# rapidshark-main-breakout-top-mk-1_7-fab.net
KiCad netlist of a schematic drawn in EAGLE
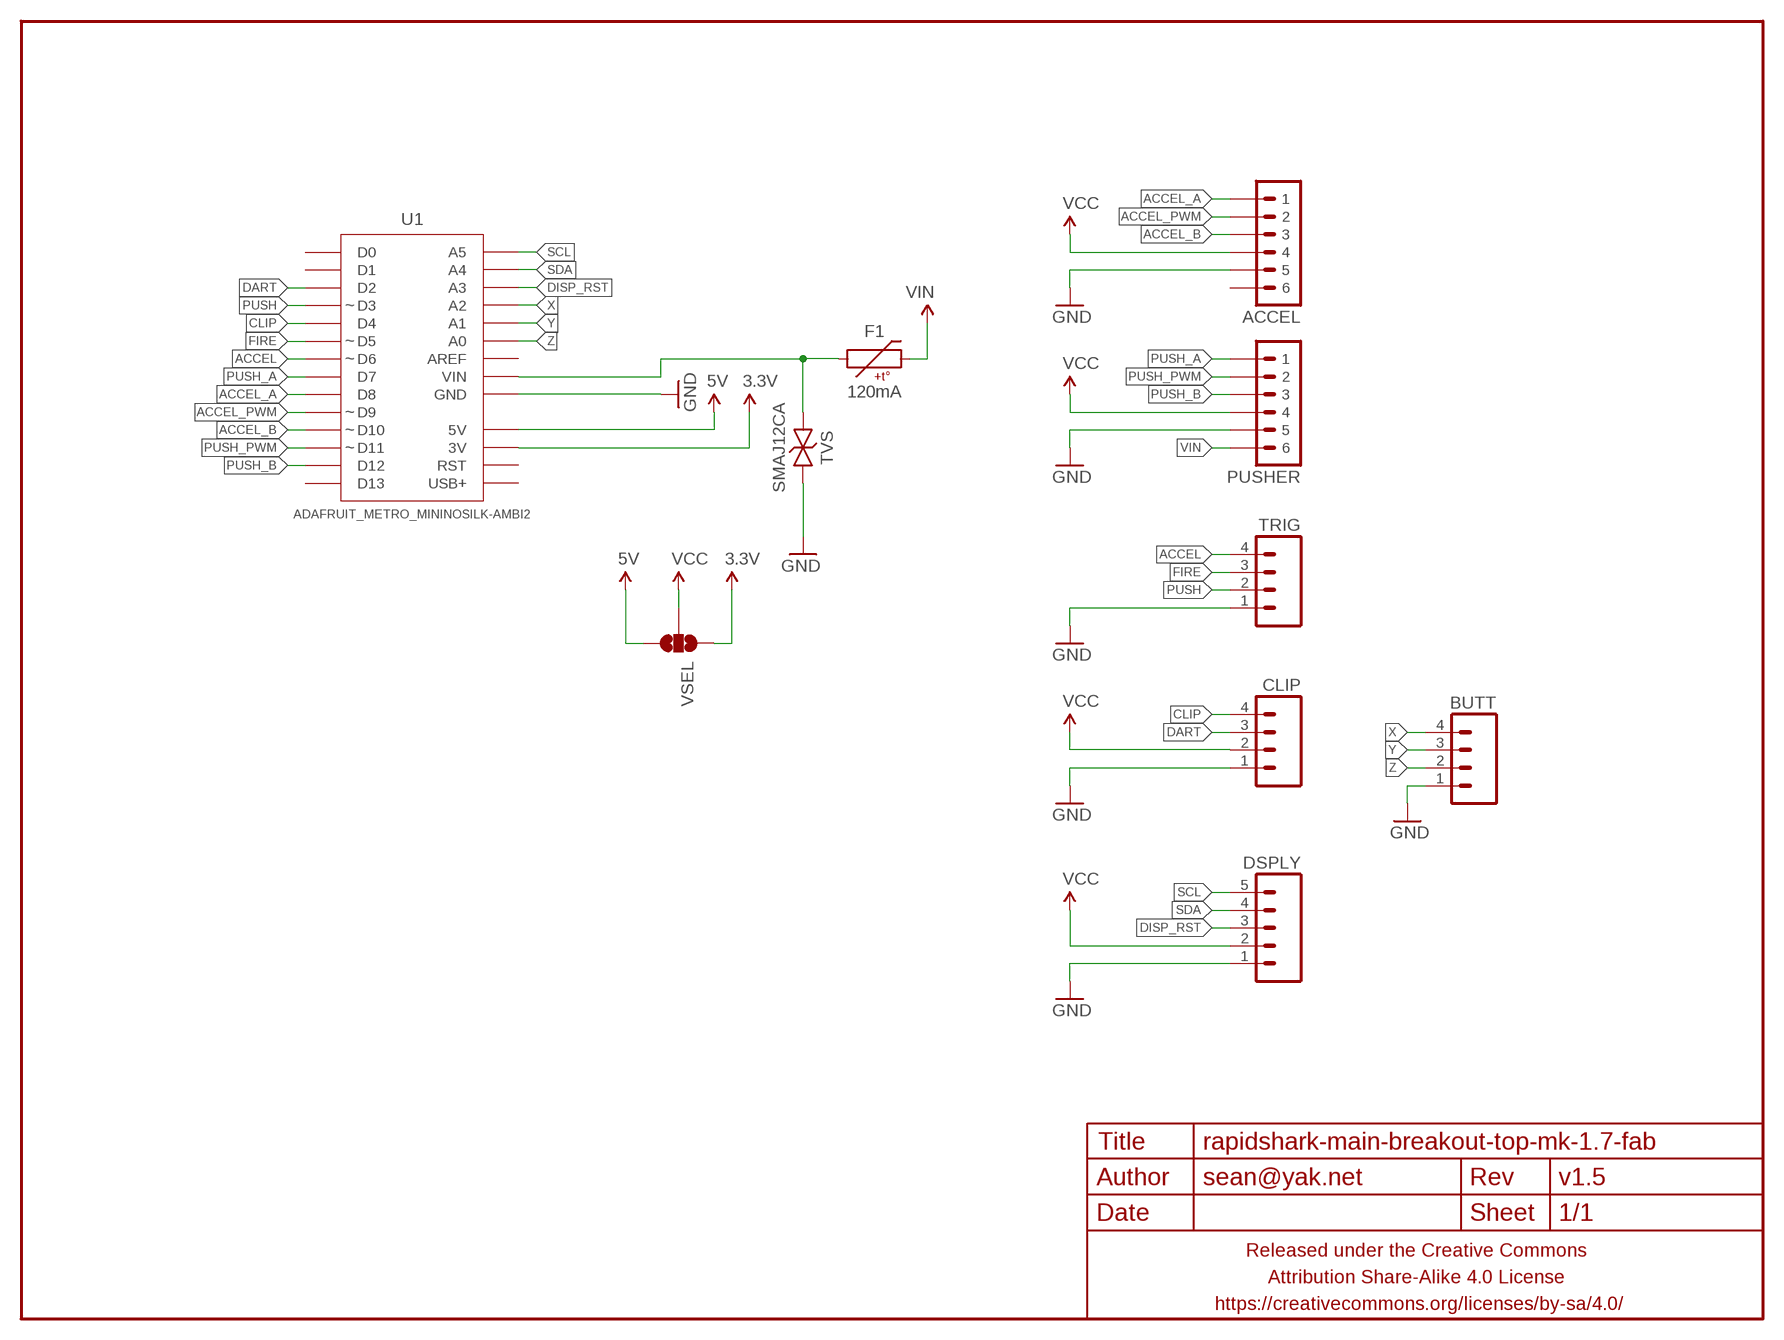
[diagram p0: schematic, sheet 1]

(export (version "E")
  (design (tool "Eeschema 10.0.6"))
  (components
    (comp (ref "ACCEL")
      (value "M06JST-PH-PTH-VERT")
      (footprint "eagle-import:JST-6-PH-VERT-PTH")
      (libsource (lib "eagle-import") (part "M06JST-PH-PTH-VERT"))
    )
    (comp (ref "BUTT")
      (value "M04JST-PTH-VERT")
      (footprint "eagle-import:JST-4-PH-VERT-PTH")
      (libsource (lib "eagle-import") (part "M04JST-PTH-VERT"))
    )
    (comp (ref "CLIP")
      (value "M04JST-PTH-VERT")
      (footprint "eagle-import:JST-4-PH-VERT-PTH")
      (libsource (lib "eagle-import") (part "M04JST-PTH-VERT"))
    )
    (comp (ref "DSPLY")
      (value "M05JST-PH-VERT-PTH")
      (footprint "eagle-import:JST-5-PH-VERT-PTH")
      (libsource (lib "eagle-import") (part "M05JST-PH-VERT-PTH"))
    )
    (comp (ref "F1")
      (value "120mA")
      (footprint "eagle-import:PTC-1206")
      (libsource (lib "eagle-import") (part "PTCSMD"))
    )
    (comp (ref "FRAME1")
      (value "FRAME-LETTERNO_PACKAGE")
      (footprint "eagle-import:DUMMY")
      (fields (field (name "DESIGNER") "sean@yak.net") (field (name "VERSION") "v1.5"))
      (libsource (lib "eagle-import") (part "FRAME-LETTERNO_PACKAGE"))
    )
    (comp (ref "PUSHER")
      (value "M06JST-PH-PTH-VERT")
      (footprint "eagle-import:JST-6-PH-VERT-PTH")
      (libsource (lib "eagle-import") (part "M06JST-PH-PTH-VERT"))
    )
    (comp (ref "TRIG")
      (value "M04JST-PTH-VERT")
      (footprint "eagle-import:JST-4-PH-VERT-PTH")
      (libsource (lib "eagle-import") (part "M04JST-PTH-VERT"))
    )
    (comp (ref "TVS")
      (value "SMAJ12CA")
      (footprint "eagle-import:SMA-DIODE-TVS-BIDIR")
      (libsource (lib "eagle-import") (part "TVSSMA"))
    )
    (comp (ref "U1")
      (value "ADAFRUIT_METRO_MININOSILK-AMBI2")
      (footprint "eagle-import:ADAFRUIT_METRO_MINI_BACK")
      (libsource (lib "eagle-import") (part "ADAFRUIT_METRO_MININOSILK-AMBI2"))
    )
    (comp (ref "VSEL")
      (value "JUMPER-PAD-3-NOFULL_BOX_SILK")
      (footprint "eagle-import:PAD-JUMPER-3-NO_YES_SILK_FULL_BOX")
      (libsource (lib "eagle-import") (part "JUMPER-PAD-3-NOFULL_BOX_SILK"))
    )
  )
  (nets
    (net (code "1") (name "3.3V") (class "Default")
      (node (ref "U1") (pin "17") (pinfunction "3V_17") (pintype "bidirectional"))
      (node (ref "VSEL") (pin "1") (pinfunction "1_1") (pintype "passive"))
    )
    (net (code "2") (name "5V") (class "Default")
      (node (ref "U1") (pin "18") (pinfunction "5V_18") (pintype "bidirectional"))
      (node (ref "VSEL") (pin "3") (pinfunction "3_3") (pintype "passive"))
    )
    (net (code "3") (name "ACCEL") (class "Default")
      (node (ref "TRIG") (pin "4") (pinfunction "4_4") (pintype "passive"))
      (node (ref "U1") (pin "7") (pinfunction "D6_7") (pintype "bidirectional"))
    )
    (net (code "4") (name "ACCEL_A") (class "Default")
      (node (ref "ACCEL") (pin "1") (pinfunction "1_1") (pintype "passive"))
      (node (ref "U1") (pin "9") (pinfunction "D8_9") (pintype "bidirectional"))
    )
    (net (code "5") (name "ACCEL_B") (class "Default")
      (node (ref "ACCEL") (pin "3") (pinfunction "3_3") (pintype "passive"))
      (node (ref "U1") (pin "11") (pinfunction "D10_11") (pintype "bidirectional"))
    )
    (net (code "6") (name "ACCEL_PWM") (class "Default")
      (node (ref "ACCEL") (pin "2") (pinfunction "2_2") (pintype "passive"))
      (node (ref "U1") (pin "10") (pinfunction "D9_10") (pintype "bidirectional"))
    )
    (net (code "7") (name "CLIP") (class "Default")
      (node (ref "CLIP") (pin "4") (pinfunction "4_4") (pintype "passive"))
      (node (ref "U1") (pin "5") (pinfunction "D4_5") (pintype "bidirectional"))
    )
    (net (code "8") (name "DART") (class "Default")
      (node (ref "CLIP") (pin "3") (pinfunction "3_3") (pintype "passive"))
      (node (ref "U1") (pin "3") (pinfunction "D2_3") (pintype "bidirectional"))
    )
    (net (code "9") (name "DISP_RST") (class "Default")
      (node (ref "DSPLY") (pin "3") (pinfunction "3_3") (pintype "passive"))
      (node (ref "U1") (pin "26") (pinfunction "A3_26") (pintype "bidirectional"))
    )
    (net (code "10") (name "FIRE") (class "Default")
      (node (ref "TRIG") (pin "3") (pinfunction "3_3") (pintype "passive"))
      (node (ref "U1") (pin "6") (pinfunction "D5_6") (pintype "bidirectional"))
    )
    (net (code "11") (name "GND") (class "Default")
      (node (ref "ACCEL") (pin "5") (pinfunction "5_5") (pintype "passive"))
      (node (ref "BUTT") (pin "1") (pinfunction "1_1") (pintype "passive"))
      (node (ref "CLIP") (pin "1") (pinfunction "1_1") (pintype "passive"))
      (node (ref "DSPLY") (pin "1") (pinfunction "1_1") (pintype "passive"))
      (node (ref "PUSHER") (pin "5") (pinfunction "5_5") (pintype "passive"))
      (node (ref "TRIG") (pin "1") (pinfunction "1_1") (pintype "passive"))
      (node (ref "TVS") (pin "1") (pinfunction "1_1") (pintype "passive"))
      (node (ref "U1") (pin "19") (pinfunction "GND_19") (pintype "bidirectional"))
      (node (ref "U1") (pin "20") (pinfunction "GND_20") (pintype "bidirectional"))
    )
    (net (code "12") (name "Net-(U1-VIN)") (class "Default")
      (node (ref "F1") (pin "1") (pinfunction "1_1") (pintype "passive"))
      (node (ref "TVS") (pin "2") (pinfunction "2_2") (pintype "passive"))
      (node (ref "U1") (pin "21") (pinfunction "VIN_21") (pintype "bidirectional"))
    )
    (net (code "13") (name "PUSH") (class "Default")
      (node (ref "TRIG") (pin "2") (pinfunction "2_2") (pintype "passive"))
      (node (ref "U1") (pin "4") (pinfunction "D3_4") (pintype "bidirectional"))
    )
    (net (code "14") (name "PUSH_A") (class "Default")
      (node (ref "PUSHER") (pin "1") (pinfunction "1_1") (pintype "passive"))
      (node (ref "U1") (pin "8") (pinfunction "D7_8") (pintype "bidirectional"))
    )
    (net (code "15") (name "PUSH_B") (class "Default")
      (node (ref "PUSHER") (pin "3") (pinfunction "3_3") (pintype "passive"))
      (node (ref "U1") (pin "13") (pinfunction "D12_13") (pintype "bidirectional"))
    )
    (net (code "16") (name "PUSH_PWM") (class "Default")
      (node (ref "PUSHER") (pin "2") (pinfunction "2_2") (pintype "passive"))
      (node (ref "U1") (pin "12") (pinfunction "D11_12") (pintype "bidirectional"))
    )
    (net (code "17") (name "SCL") (class "Default")
      (node (ref "DSPLY") (pin "5") (pinfunction "5_5") (pintype "passive"))
      (node (ref "U1") (pin "28") (pinfunction "A5_28") (pintype "bidirectional"))
    )
    (net (code "18") (name "SDA") (class "Default")
      (node (ref "DSPLY") (pin "4") (pinfunction "4_4") (pintype "passive"))
      (node (ref "U1") (pin "27") (pinfunction "A4_27") (pintype "bidirectional"))
    )
    (net (code "19") (name "VCC") (class "Default")
      (node (ref "ACCEL") (pin "4") (pinfunction "4_4") (pintype "passive"))
      (node (ref "CLIP") (pin "2") (pinfunction "2_2") (pintype "passive"))
      (node (ref "DSPLY") (pin "2") (pinfunction "2_2") (pintype "passive"))
      (node (ref "PUSHER") (pin "4") (pinfunction "4_4") (pintype "passive"))
      (node (ref "VSEL") (pin "2") (pinfunction "2_2") (pintype "passive"))
    )
    (net (code "20") (name "VIN") (class "Default")
      (node (ref "F1") (pin "2") (pinfunction "2_2") (pintype "passive"))
      (node (ref "PUSHER") (pin "6") (pinfunction "6_6") (pintype "passive"))
    )
    (net (code "21") (name "X") (class "Default")
      (node (ref "BUTT") (pin "4") (pinfunction "4_4") (pintype "passive"))
      (node (ref "U1") (pin "25") (pinfunction "A2_25") (pintype "bidirectional"))
    )
    (net (code "22") (name "Y") (class "Default")
      (node (ref "BUTT") (pin "3") (pinfunction "3_3") (pintype "passive"))
      (node (ref "U1") (pin "24") (pinfunction "A1_24") (pintype "bidirectional"))
    )
    (net (code "23") (name "Z") (class "Default")
      (node (ref "BUTT") (pin "2") (pinfunction "2_2") (pintype "passive"))
      (node (ref "U1") (pin "23") (pinfunction "A0_23") (pintype "bidirectional"))
    )
    (net (code "24") (name "unconnected-(ACCEL-Pad6)") (class "Default")
      (node (ref "ACCEL") (pin "6") (pinfunction "6_6") (pintype "passive"))
    )
    (net (code "25") (name "unconnected-(U1-AREF-Pad22)") (class "Default")
      (node (ref "U1") (pin "22") (pinfunction "AREF_22") (pintype "bidirectional"))
    )
    (net (code "26") (name "unconnected-(U1-D0-Pad1)") (class "Default")
      (node (ref "U1") (pin "1") (pinfunction "D0_1") (pintype "bidirectional"))
    )
    (net (code "27") (name "unconnected-(U1-D1-Pad2)") (class "Default")
      (node (ref "U1") (pin "2") (pinfunction "D1_2") (pintype "bidirectional"))
    )
    (net (code "28") (name "unconnected-(U1-D13-Pad14)") (class "Default")
      (node (ref "U1") (pin "14") (pinfunction "D13_14") (pintype "bidirectional"))
    )
    (net (code "29") (name "unconnected-(U1-RST-Pad16)") (class "Default")
      (node (ref "U1") (pin "16") (pinfunction "RST_16") (pintype "bidirectional"))
    )
    (net (code "30") (name "unconnected-(U1-USB+-Pad15)") (class "Default")
      (node (ref "U1") (pin "15") (pinfunction "USB+_15") (pintype "bidirectional"))
    )
  )
)
